# 1_cpu_control.net
KiCad netlist of a schematic drawn in EAGLE
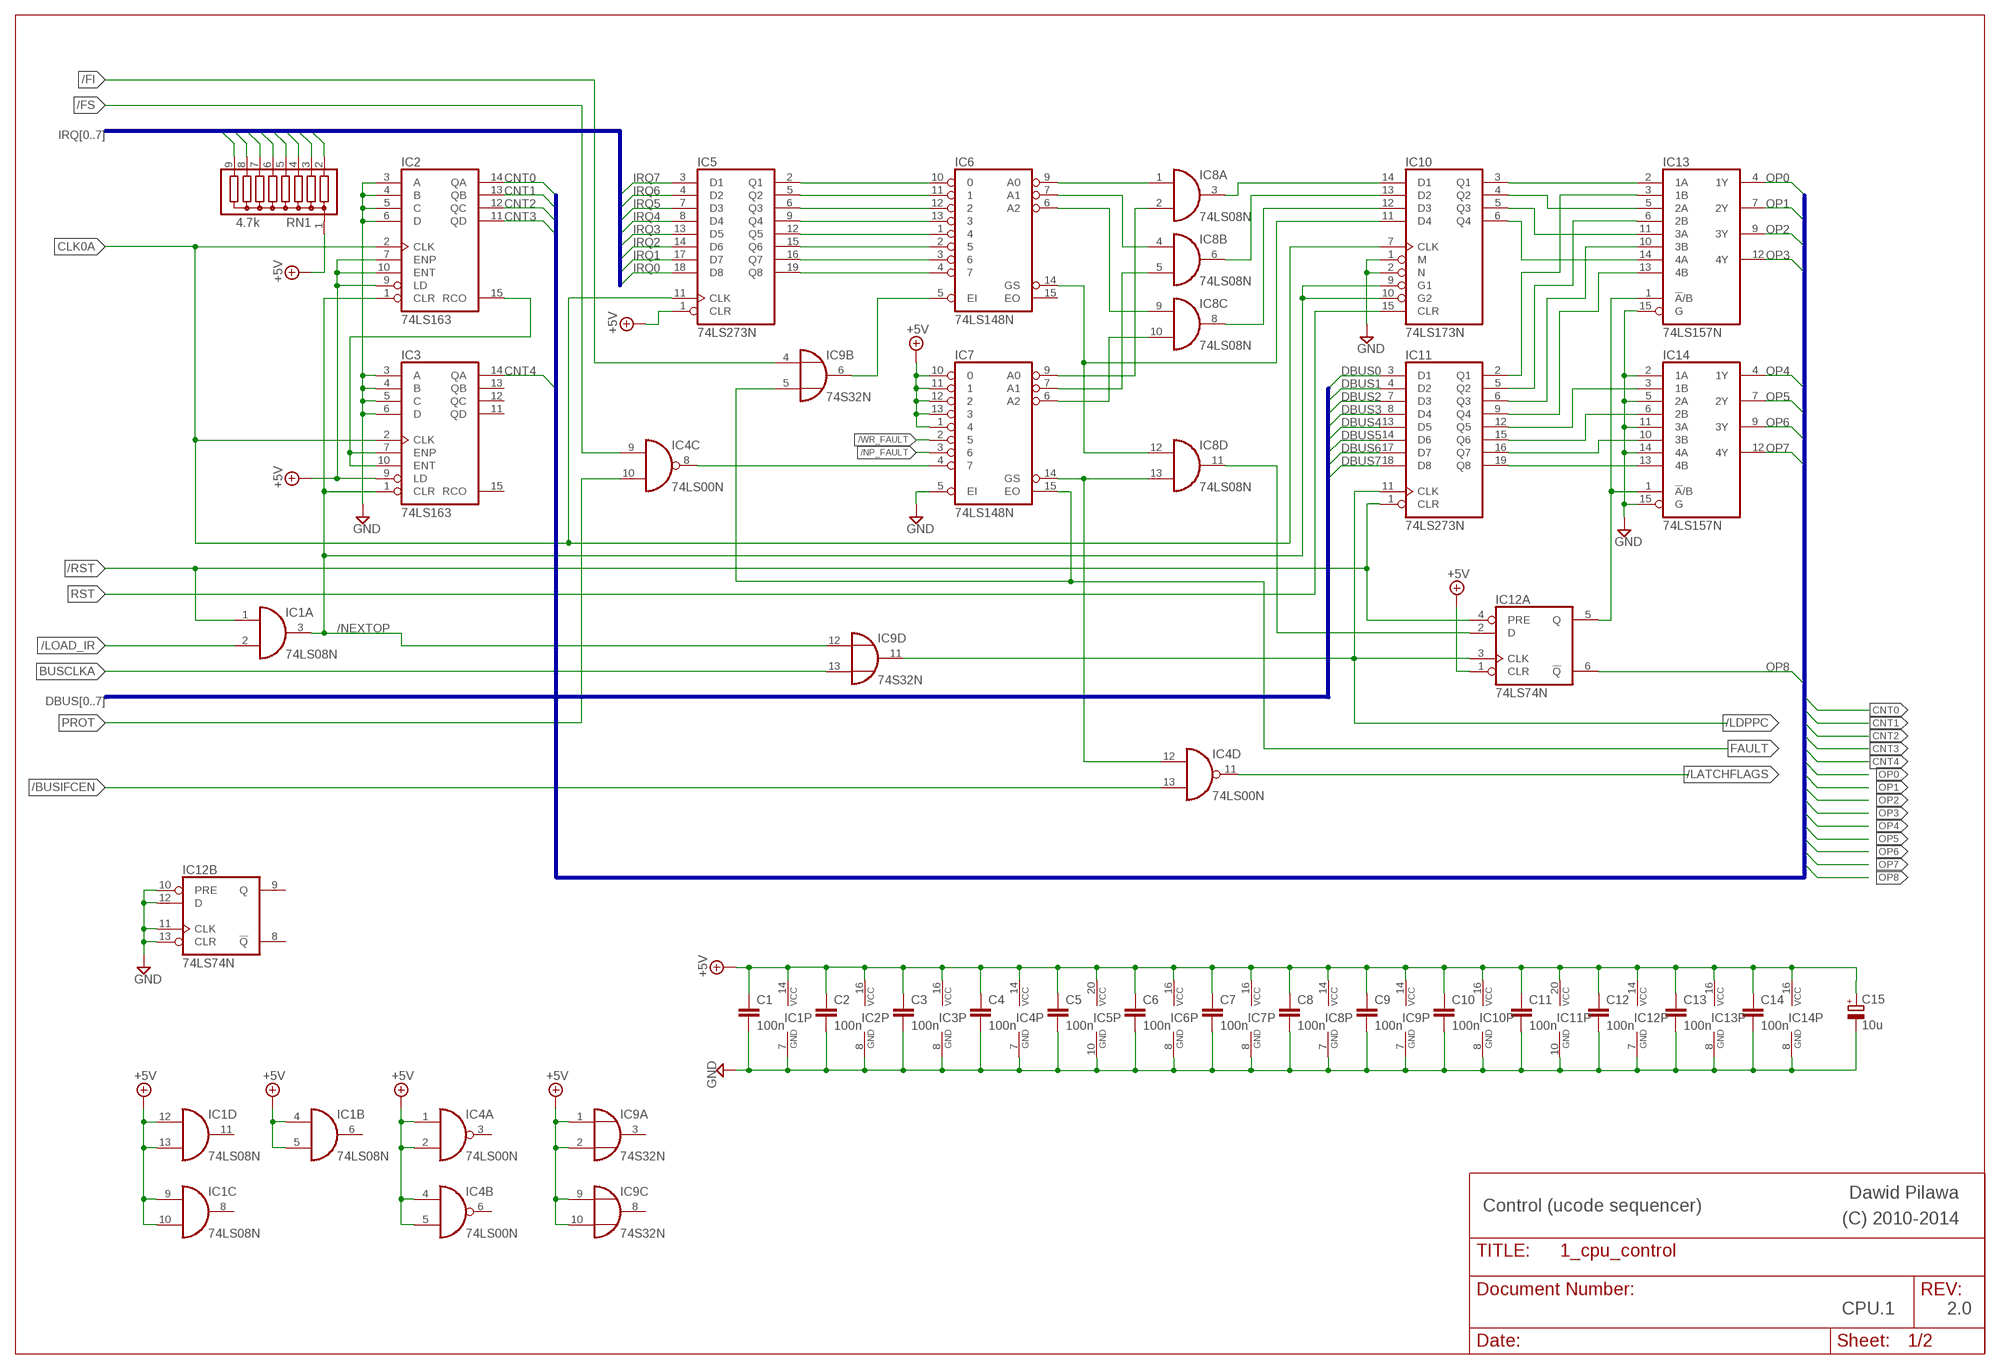
[diagram p0: schematic, sheet 1]
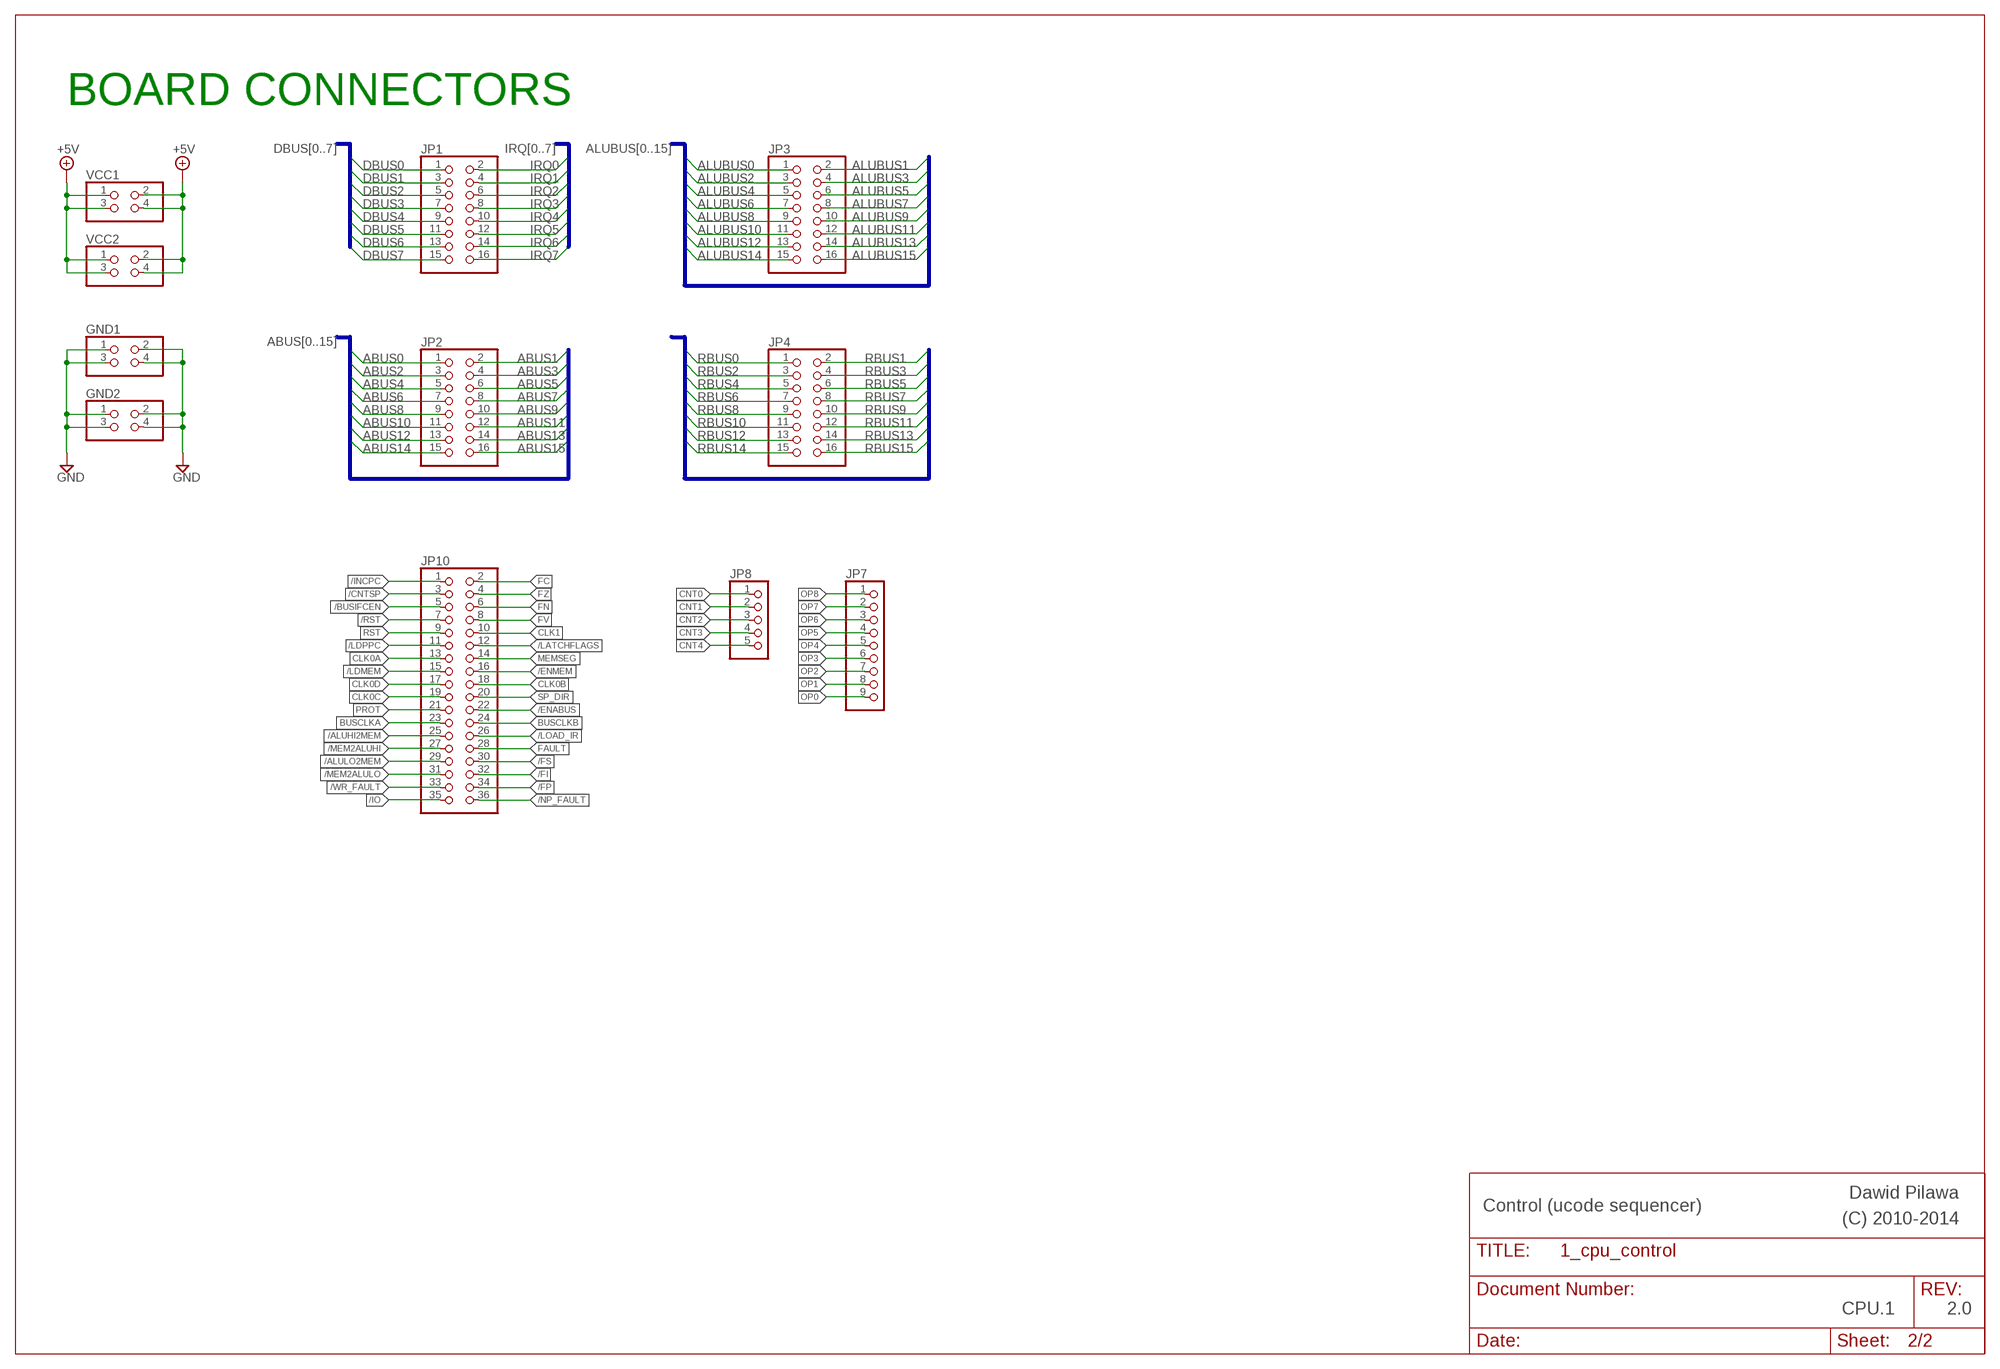
[diagram p1: schematic, sheet 2]

(export (version "E")
  (design (tool "Eeschema 10.0.6"))
  (components
    (comp (ref "GND1")
      (value "PINHD-2X2")
      (footprint "eagle-import:2X02")
      (libsource (lib "eagle-import") (part "PINHD-2X2"))
    )
    (comp (ref "GND2")
      (value "PINHD-2X2")
      (footprint "eagle-import:2X02")
      (libsource (lib "eagle-import") (part "PINHD-2X2"))
    )
    (comp (ref "JP1")
      (value "PINHD-2X8")
      (footprint "eagle-import:2X08")
      (libsource (lib "eagle-import") (part "PINHD-2X8"))
    )
    (comp (ref "JP2")
      (value "PINHD-2X8")
      (footprint "eagle-import:2X08")
      (libsource (lib "eagle-import") (part "PINHD-2X8"))
    )
    (comp (ref "JP3")
      (value "PINHD-2X8")
      (footprint "eagle-import:2X08")
      (libsource (lib "eagle-import") (part "PINHD-2X8"))
    )
    (comp (ref "JP4")
      (value "PINHD-2X8")
      (footprint "eagle-import:2X08")
      (libsource (lib "eagle-import") (part "PINHD-2X8"))
    )
    (comp (ref "JP7")
      (value "PINHD-1X9")
      (footprint "eagle-import:1X09")
      (libsource (lib "eagle-import") (part "PINHD-1X9"))
    )
    (comp (ref "JP8")
      (value "PINHD-1X5")
      (footprint "eagle-import:1X05")
      (libsource (lib "eagle-import") (part "PINHD-1X5"))
    )
    (comp (ref "JP10")
      (value "PINHD-2X18")
      (footprint "eagle-import:2X18")
      (libsource (lib "eagle-import") (part "PINHD-2X18"))
    )
    (comp (ref "VCC1")
      (value "PINHD-2X2")
      (footprint "eagle-import:2X02")
      (libsource (lib "eagle-import") (part "PINHD-2X2"))
    )
    (comp (ref "VCC2")
      (value "PINHD-2X2")
      (footprint "eagle-import:2X02")
      (libsource (lib "eagle-import") (part "PINHD-2X2"))
    )
    (comp (ref "C1")
      (value "100n")
      (footprint "eagle-import:C050-024X044")
      (libsource (lib "eagle-import") (part "C-EU050-024X044"))
    )
    (comp (ref "C2")
      (value "100n")
      (footprint "eagle-import:C050-024X044")
      (libsource (lib "eagle-import") (part "C-EU050-024X044"))
    )
    (comp (ref "C3")
      (value "100n")
      (footprint "eagle-import:C050-024X044")
      (libsource (lib "eagle-import") (part "C-EU050-024X044"))
    )
    (comp (ref "C4")
      (value "100n")
      (footprint "eagle-import:C050-024X044")
      (libsource (lib "eagle-import") (part "C-EU050-024X044"))
    )
    (comp (ref "C5")
      (value "100n")
      (footprint "eagle-import:C050-024X044")
      (libsource (lib "eagle-import") (part "C-EU050-024X044"))
    )
    (comp (ref "C6")
      (value "100n")
      (footprint "eagle-import:C050-024X044")
      (libsource (lib "eagle-import") (part "C-EU050-024X044"))
    )
    (comp (ref "C7")
      (value "100n")
      (footprint "eagle-import:C050-024X044")
      (libsource (lib "eagle-import") (part "C-EU050-024X044"))
    )
    (comp (ref "C8")
      (value "100n")
      (footprint "eagle-import:C050-024X044")
      (libsource (lib "eagle-import") (part "C-EU050-024X044"))
    )
    (comp (ref "C9")
      (value "100n")
      (footprint "eagle-import:C050-024X044")
      (libsource (lib "eagle-import") (part "C-EU050-024X044"))
    )
    (comp (ref "C10")
      (value "100n")
      (footprint "eagle-import:C050-024X044")
      (libsource (lib "eagle-import") (part "C-EU050-024X044"))
    )
    (comp (ref "C11")
      (value "100n")
      (footprint "eagle-import:C050-024X044")
      (libsource (lib "eagle-import") (part "C-EU050-024X044"))
    )
    (comp (ref "C12")
      (value "100n")
      (footprint "eagle-import:C050-024X044")
      (libsource (lib "eagle-import") (part "C-EU050-024X044"))
    )
    (comp (ref "C13")
      (value "100n")
      (footprint "eagle-import:C050-024X044")
      (libsource (lib "eagle-import") (part "C-EU050-024X044"))
    )
    (comp (ref "C14")
      (value "100n")
      (footprint "eagle-import:C050-024X044")
      (libsource (lib "eagle-import") (part "C-EU050-024X044"))
    )
    (comp (ref "C15")
      (value "10u")
      (footprint "eagle-import:E5-6")
      (libsource (lib "eagle-import") (part "CPOL-EUE5-6"))
    )
    (comp (ref "IC1")
      (value "74LS08N")
      (footprint "eagle-import:DIL14")
      (libsource (lib "eagle-import") (part "7408NLS"))
    )
    (comp (ref "IC2")
      (value "74LS163")
      (footprint "eagle-import:DIL16")
      (libsource (lib "eagle-import") (part "74160N"))
    )
    (comp (ref "IC3")
      (value "74LS163")
      (footprint "eagle-import:DIL16")
      (libsource (lib "eagle-import") (part "74160N"))
    )
    (comp (ref "IC4")
      (value "74LS00N")
      (footprint "eagle-import:DIL14")
      (libsource (lib "eagle-import") (part "7400NLS"))
    )
    (comp (ref "IC5")
      (value "74LS273N")
      (footprint "eagle-import:DIL20")
      (libsource (lib "eagle-import") (part "74273N"))
    )
    (comp (ref "IC6")
      (value "74LS148N")
      (footprint "eagle-import:DIL16")
      (libsource (lib "eagle-import") (part "74148NLS"))
    )
    (comp (ref "IC7")
      (value "74LS148N")
      (footprint "eagle-import:DIL16")
      (libsource (lib "eagle-import") (part "74148NLS"))
    )
    (comp (ref "IC8")
      (value "74LS08N")
      (footprint "eagle-import:DIL14")
      (libsource (lib "eagle-import") (part "7408NLS"))
    )
    (comp (ref "IC9")
      (value "74S32N")
      (footprint "eagle-import:DIL14")
      (libsource (lib "eagle-import") (part "7432NS"))
    )
    (comp (ref "IC10")
      (value "74LS173N")
      (footprint "eagle-import:DIL16")
      (libsource (lib "eagle-import") (part "74173NLS"))
    )
    (comp (ref "IC11")
      (value "74LS273N")
      (footprint "eagle-import:DIL20")
      (libsource (lib "eagle-import") (part "74273N"))
    )
    (comp (ref "IC12")
      (value "74LS74N")
      (footprint "eagle-import:DIL14")
      (libsource (lib "eagle-import") (part "7474NLS"))
    )
    (comp (ref "IC13")
      (value "74LS157N")
      (footprint "eagle-import:DIL16")
      (libsource (lib "eagle-import") (part "74157NLS"))
    )
    (comp (ref "IC14")
      (value "74LS157N")
      (footprint "eagle-import:DIL16")
      (libsource (lib "eagle-import") (part "74157NLS"))
    )
    (comp (ref "RN1")
      (value "4.7k")
      (footprint "eagle-import:SIL9")
      (libsource (lib "eagle-import") (part "G08R"))
    )
  )
  (nets
    (net (code "1") (name "+5V") (class "Default")
      (node (ref "C1") (pin "1") (pinfunction "1_1") (pintype "passive"))
      (node (ref "C10") (pin "1") (pinfunction "1_1") (pintype "passive"))
      (node (ref "C11") (pin "1") (pinfunction "1_1") (pintype "passive"))
      (node (ref "C12") (pin "1") (pinfunction "1_1") (pintype "passive"))
      (node (ref "C13") (pin "1") (pinfunction "1_1") (pintype "passive"))
      (node (ref "C14") (pin "1") (pinfunction "1_1") (pintype "passive"))
      (node (ref "C15") (pin "+") (pinfunction "+_+") (pintype "passive"))
      (node (ref "C2") (pin "1") (pinfunction "1_1") (pintype "passive"))
      (node (ref "C3") (pin "1") (pinfunction "1_1") (pintype "passive"))
      (node (ref "C4") (pin "1") (pinfunction "1_1") (pintype "passive"))
      (node (ref "C5") (pin "1") (pinfunction "1_1") (pintype "passive"))
      (node (ref "C6") (pin "1") (pinfunction "1_1") (pintype "passive"))
      (node (ref "C7") (pin "1") (pinfunction "1_1") (pintype "passive"))
      (node (ref "C8") (pin "1") (pinfunction "1_1") (pintype "passive"))
      (node (ref "C9") (pin "1") (pinfunction "1_1") (pintype "passive"))
      (node (ref "IC1") (pin "10") (pinfunction "I1_10") (pintype "input"))
      (node (ref "IC1") (pin "12") (pinfunction "I0_12") (pintype "input"))
      (node (ref "IC1") (pin "13") (pinfunction "I1_13") (pintype "input"))
      (node (ref "IC1") (pin "14") (pinfunction "VCC_14") (pintype "power_in"))
      (node (ref "IC1") (pin "4") (pinfunction "I0_4") (pintype "input"))
      (node (ref "IC1") (pin "5") (pinfunction "I1_5") (pintype "input"))
      (node (ref "IC1") (pin "9") (pinfunction "I0_9") (pintype "input"))
      (node (ref "IC10") (pin "16") (pinfunction "VCC_16") (pintype "power_in"))
      (node (ref "IC11") (pin "20") (pinfunction "VCC_20") (pintype "power_in"))
      (node (ref "IC12") (pin "1") (pinfunction "CLR_1") (pintype "input"))
      (node (ref "IC12") (pin "14") (pinfunction "VCC_14") (pintype "power_in"))
      (node (ref "IC13") (pin "16") (pinfunction "VCC_16") (pintype "power_in"))
      (node (ref "IC14") (pin "16") (pinfunction "VCC_16") (pintype "power_in"))
      (node (ref "IC2") (pin "10") (pinfunction "ENT_10") (pintype "input"))
      (node (ref "IC2") (pin "16") (pinfunction "VCC_16") (pintype "power_in"))
      (node (ref "IC2") (pin "7") (pinfunction "ENP_7") (pintype "input"))
      (node (ref "IC2") (pin "9") (pinfunction "LD_9") (pintype "input"))
      (node (ref "IC3") (pin "16") (pinfunction "VCC_16") (pintype "power_in"))
      (node (ref "IC3") (pin "9") (pinfunction "LD_9") (pintype "input"))
      (node (ref "IC4") (pin "1") (pinfunction "I0_1") (pintype "input"))
      (node (ref "IC4") (pin "14") (pinfunction "VCC_14") (pintype "power_in"))
      (node (ref "IC4") (pin "2") (pinfunction "I1_2") (pintype "input"))
      (node (ref "IC4") (pin "4") (pinfunction "I0_4") (pintype "input"))
      (node (ref "IC4") (pin "5") (pinfunction "I1_5") (pintype "input"))
      (node (ref "IC5") (pin "1") (pinfunction "CLR_1") (pintype "input"))
      (node (ref "IC5") (pin "20") (pinfunction "VCC_20") (pintype "power_in"))
      (node (ref "IC6") (pin "16") (pinfunction "VCC_16") (pintype "power_in"))
      (node (ref "IC7") (pin "1") (pinfunction "4_1") (pintype "input"))
      (node (ref "IC7") (pin "10") (pinfunction "0_10") (pintype "input"))
      (node (ref "IC7") (pin "11") (pinfunction "1_11") (pintype "input"))
      (node (ref "IC7") (pin "12") (pinfunction "2_12") (pintype "input"))
      (node (ref "IC7") (pin "13") (pinfunction "3_13") (pintype "input"))
      (node (ref "IC7") (pin "16") (pinfunction "VCC_16") (pintype "power_in"))
      (node (ref "IC8") (pin "14") (pinfunction "VCC_14") (pintype "power_in"))
      (node (ref "IC9") (pin "1") (pinfunction "I0_1") (pintype "input"))
      (node (ref "IC9") (pin "10") (pinfunction "I1_10") (pintype "input"))
      (node (ref "IC9") (pin "14") (pinfunction "VCC_14") (pintype "power_in"))
      (node (ref "IC9") (pin "2") (pinfunction "I1_2") (pintype "input"))
      (node (ref "IC9") (pin "9") (pinfunction "I0_9") (pintype "input"))
      (node (ref "RN1") (pin "1") (pinfunction "1_1") (pintype "passive"))
      (node (ref "VCC1") (pin "1") (pinfunction "1_1") (pintype "passive"))
      (node (ref "VCC1") (pin "2") (pinfunction "2_2") (pintype "passive"))
      (node (ref "VCC1") (pin "3") (pinfunction "3_3") (pintype "passive"))
      (node (ref "VCC1") (pin "4") (pinfunction "4_4") (pintype "passive"))
      (node (ref "VCC2") (pin "1") (pinfunction "1_1") (pintype "passive"))
      (node (ref "VCC2") (pin "2") (pinfunction "2_2") (pintype "passive"))
      (node (ref "VCC2") (pin "3") (pinfunction "3_3") (pintype "passive"))
      (node (ref "VCC2") (pin "4") (pinfunction "4_4") (pintype "passive"))
    )
    (net (code "8") (name "ABUS0") (class "Default")
      (node (ref "JP2") (pin "1") (pinfunction "1_1") (pintype "passive"))
    )
    (net (code "9") (name "ABUS1") (class "Default")
      (node (ref "JP2") (pin "2") (pinfunction "2_2") (pintype "passive"))
    )
    (net (code "10") (name "ABUS2") (class "Default")
      (node (ref "JP2") (pin "3") (pinfunction "3_3") (pintype "passive"))
    )
    (net (code "11") (name "ABUS3") (class "Default")
      (node (ref "JP2") (pin "4") (pinfunction "4_4") (pintype "passive"))
    )
    (net (code "12") (name "ABUS4") (class "Default")
      (node (ref "JP2") (pin "5") (pinfunction "5_5") (pintype "passive"))
    )
    (net (code "13") (name "ABUS5") (class "Default")
      (node (ref "JP2") (pin "6") (pinfunction "6_6") (pintype "passive"))
    )
    (net (code "14") (name "ABUS6") (class "Default")
      (node (ref "JP2") (pin "7") (pinfunction "7_7") (pintype "passive"))
    )
    (net (code "15") (name "ABUS7") (class "Default")
      (node (ref "JP2") (pin "8") (pinfunction "8_8") (pintype "passive"))
    )
    (net (code "16") (name "ABUS8") (class "Default")
      (node (ref "JP2") (pin "9") (pinfunction "9_9") (pintype "passive"))
    )
    (net (code "17") (name "ABUS9") (class "Default")
      (node (ref "JP2") (pin "10") (pinfunction "10_10") (pintype "passive"))
    )
    (net (code "18") (name "ABUS10") (class "Default")
      (node (ref "JP2") (pin "11") (pinfunction "11_11") (pintype "passive"))
    )
    (net (code "19") (name "ABUS11") (class "Default")
      (node (ref "JP2") (pin "12") (pinfunction "12_12") (pintype "passive"))
    )
    (net (code "20") (name "ABUS12") (class "Default")
      (node (ref "JP2") (pin "13") (pinfunction "13_13") (pintype "passive"))
    )
    (net (code "21") (name "ABUS13") (class "Default")
      (node (ref "JP2") (pin "14") (pinfunction "14_14") (pintype "passive"))
    )
    (net (code "22") (name "ABUS14") (class "Default")
      (node (ref "JP2") (pin "15") (pinfunction "15_15") (pintype "passive"))
    )
    (net (code "23") (name "ABUS15") (class "Default")
      (node (ref "JP2") (pin "16") (pinfunction "16_16") (pintype "passive"))
    )
    (net (code "24") (name "ALUBUS0") (class "Default")
      (node (ref "JP3") (pin "1") (pinfunction "1_1") (pintype "passive"))
    )
    (net (code "25") (name "ALUBUS1") (class "Default")
      (node (ref "JP3") (pin "2") (pinfunction "2_2") (pintype "passive"))
    )
    (net (code "26") (name "ALUBUS2") (class "Default")
      (node (ref "JP3") (pin "3") (pinfunction "3_3") (pintype "passive"))
    )
    (net (code "27") (name "ALUBUS3") (class "Default")
      (node (ref "JP3") (pin "4") (pinfunction "4_4") (pintype "passive"))
    )
    (net (code "28") (name "ALUBUS4") (class "Default")
      (node (ref "JP3") (pin "5") (pinfunction "5_5") (pintype "passive"))
    )
    (net (code "29") (name "ALUBUS5") (class "Default")
      (node (ref "JP3") (pin "6") (pinfunction "6_6") (pintype "passive"))
    )
    (net (code "30") (name "ALUBUS6") (class "Default")
      (node (ref "JP3") (pin "7") (pinfunction "7_7") (pintype "passive"))
    )
    (net (code "31") (name "ALUBUS7") (class "Default")
      (node (ref "JP3") (pin "8") (pinfunction "8_8") (pintype "passive"))
    )
    (net (code "32") (name "ALUBUS8") (class "Default")
      (node (ref "JP3") (pin "9") (pinfunction "9_9") (pintype "passive"))
    )
    (net (code "33") (name "ALUBUS9") (class "Default")
      (node (ref "JP3") (pin "10") (pinfunction "10_10") (pintype "passive"))
    )
    (net (code "34") (name "ALUBUS10") (class "Default")
      (node (ref "JP3") (pin "11") (pinfunction "11_11") (pintype "passive"))
    )
    (net (code "35") (name "ALUBUS11") (class "Default")
      (node (ref "JP3") (pin "12") (pinfunction "12_12") (pintype "passive"))
    )
    (net (code "36") (name "ALUBUS12") (class "Default")
      (node (ref "JP3") (pin "13") (pinfunction "13_13") (pintype "passive"))
    )
    (net (code "37") (name "ALUBUS13") (class "Default")
      (node (ref "JP3") (pin "14") (pinfunction "14_14") (pintype "passive"))
    )
    (net (code "38") (name "ALUBUS14") (class "Default")
      (node (ref "JP3") (pin "15") (pinfunction "15_15") (pintype "passive"))
    )
    (net (code "39") (name "ALUBUS15") (class "Default")
      (node (ref "JP3") (pin "16") (pinfunction "16_16") (pintype "passive"))
    )
    (net (code "40") (name "BUSCLKA") (class "Default")
      (node (ref "IC9") (pin "13") (pinfunction "I1_13") (pintype "input"))
      (node (ref "JP10") (pin "23") (pinfunction "23_23") (pintype "passive"))
    )
    (net (code "41") (name "BUSCLKB") (class "Default")
      (node (ref "JP10") (pin "24") (pinfunction "24_24") (pintype "passive"))
    )
    (net (code "42") (name "CLK0A") (class "Default")
      (node (ref "IC10") (pin "7") (pinfunction "CLK_7") (pintype "input"))
      (node (ref "IC2") (pin "2") (pinfunction "CLK_2") (pintype "input"))
      (node (ref "IC3") (pin "2") (pinfunction "CLK_2") (pintype "input"))
      (node (ref "IC5") (pin "11") (pinfunction "CLK_11") (pintype "input"))
      (node (ref "JP10") (pin "13") (pinfunction "13_13") (pintype "passive"))
    )
    (net (code "43") (name "CLK0B") (class "Default")
      (node (ref "JP10") (pin "18") (pinfunction "18_18") (pintype "passive"))
    )
    (net (code "44") (name "CLK0C") (class "Default")
      (node (ref "JP10") (pin "19") (pinfunction "19_19") (pintype "passive"))
    )
    (net (code "45") (name "CLK0D") (class "Default")
      (node (ref "JP10") (pin "17") (pinfunction "17_17") (pintype "passive"))
    )
    (net (code "46") (name "CLK1") (class "Default")
      (node (ref "JP10") (pin "10") (pinfunction "10_10") (pintype "passive"))
    )
    (net (code "47") (name "CNT0") (class "Default")
      (node (ref "IC2") (pin "14") (pinfunction "QA_14") (pintype "output"))
      (node (ref "JP8") (pin "1") (pinfunction "1_1") (pintype "passive"))
    )
    (net (code "48") (name "CNT1") (class "Default")
      (node (ref "IC2") (pin "13") (pinfunction "QB_13") (pintype "output"))
      (node (ref "JP8") (pin "2") (pinfunction "2_2") (pintype "passive"))
    )
    (net (code "49") (name "CNT2") (class "Default")
      (node (ref "IC2") (pin "12") (pinfunction "QC_12") (pintype "output"))
      (node (ref "JP8") (pin "3") (pinfunction "3_3") (pintype "passive"))
    )
    (net (code "50") (name "CNT3") (class "Default")
      (node (ref "IC2") (pin "11") (pinfunction "QD_11") (pintype "output"))
      (node (ref "JP8") (pin "4") (pinfunction "4_4") (pintype "passive"))
    )
    (net (code "51") (name "CNT4") (class "Default")
      (node (ref "IC3") (pin "14") (pinfunction "QA_14") (pintype "output"))
      (node (ref "JP8") (pin "5") (pinfunction "5_5") (pintype "passive"))
    )
    (net (code "52") (name "DBUS0") (class "Default")
      (node (ref "IC11") (pin "3") (pinfunction "D1_3") (pintype "input"))
      (node (ref "JP1") (pin "1") (pinfunction "1_1") (pintype "passive"))
    )
    (net (code "53") (name "DBUS1") (class "Default")
      (node (ref "IC11") (pin "4") (pinfunction "D2_4") (pintype "input"))
      (node (ref "JP1") (pin "3") (pinfunction "3_3") (pintype "passive"))
    )
    (net (code "54") (name "DBUS2") (class "Default")
      (node (ref "IC11") (pin "7") (pinfunction "D3_7") (pintype "input"))
      (node (ref "JP1") (pin "5") (pinfunction "5_5") (pintype "passive"))
    )
    (net (code "55") (name "DBUS3") (class "Default")
      (node (ref "IC11") (pin "8") (pinfunction "D4_8") (pintype "input"))
      (node (ref "JP1") (pin "7") (pinfunction "7_7") (pintype "passive"))
    )
    (net (code "56") (name "DBUS4") (class "Default")
      (node (ref "IC11") (pin "13") (pinfunction "D5_13") (pintype "input"))
      (node (ref "JP1") (pin "9") (pinfunction "9_9") (pintype "passive"))
    )
    (net (code "57") (name "DBUS5") (class "Default")
      (node (ref "IC11") (pin "14") (pinfunction "D6_14") (pintype "input"))
      (node (ref "JP1") (pin "11") (pinfunction "11_11") (pintype "passive"))
    )
    (net (code "58") (name "DBUS6") (class "Default")
      (node (ref "IC11") (pin "17") (pinfunction "D7_17") (pintype "input"))
      (node (ref "JP1") (pin "13") (pinfunction "13_13") (pintype "passive"))
    )
    (net (code "59") (name "DBUS7") (class "Default")
      (node (ref "IC11") (pin "18") (pinfunction "D8_18") (pintype "input"))
      (node (ref "JP1") (pin "15") (pinfunction "15_15") (pintype "passive"))
    )
    (net (code "60") (name "FAULT") (class "Default")
      (node (ref "IC7") (pin "15") (pinfunction "EO_15") (pintype "output"))
      (node (ref "IC9") (pin "5") (pinfunction "I1_5") (pintype "input"))
      (node (ref "JP10") (pin "28") (pinfunction "28_28") (pintype "passive"))
    )
    (net (code "61") (name "FC") (class "Default")
      (node (ref "JP10") (pin "2") (pinfunction "2_2") (pintype "passive"))
    )
    (net (code "62") (name "FN") (class "Default")
      (node (ref "JP10") (pin "6") (pinfunction "6_6") (pintype "passive"))
    )
    (net (code "63") (name "FV") (class "Default")
      (node (ref "JP10") (pin "8") (pinfunction "8_8") (pintype "passive"))
    )
    (net (code "64") (name "FZ") (class "Default")
      (node (ref "JP10") (pin "4") (pinfunction "4_4") (pintype "passive"))
    )
    (net (code "65") (name "GND") (class "Default")
      (node (ref "C1") (pin "2") (pinfunction "2_2") (pintype "passive"))
      (node (ref "C10") (pin "2") (pinfunction "2_2") (pintype "passive"))
      (node (ref "C11") (pin "2") (pinfunction "2_2") (pintype "passive"))
      (node (ref "C12") (pin "2") (pinfunction "2_2") (pintype "passive"))
      (node (ref "C13") (pin "2") (pinfunction "2_2") (pintype "passive"))
      (node (ref "C14") (pin "2") (pinfunction "2_2") (pintype "passive"))
      (node (ref "C15") (pin "-") (pinfunction "-_-") (pintype "passive"))
      (node (ref "C2") (pin "2") (pinfunction "2_2") (pintype "passive"))
      (node (ref "C3") (pin "2") (pinfunction "2_2") (pintype "passive"))
      (node (ref "C4") (pin "2") (pinfunction "2_2") (pintype "passive"))
      (node (ref "C5") (pin "2") (pinfunction "2_2") (pintype "passive"))
      (node (ref "C6") (pin "2") (pinfunction "2_2") (pintype "passive"))
      (node (ref "C7") (pin "2") (pinfunction "2_2") (pintype "passive"))
      (node (ref "C8") (pin "2") (pinfunction "2_2") (pintype "passive"))
      (node (ref "C9") (pin "2") (pinfunction "2_2") (pintype "passive"))
      (node (ref "GND1") (pin "1") (pinfunction "1_1") (pintype "passive"))
      (node (ref "GND1") (pin "2") (pinfunction "2_2") (pintype "passive"))
      (node (ref "GND1") (pin "3") (pinfunction "3_3") (pintype "passive"))
      (node (ref "GND1") (pin "4") (pinfunction "4_4") (pintype "passive"))
      (node (ref "GND2") (pin "1") (pinfunction "1_1") (pintype "passive"))
      (node (ref "GND2") (pin "2") (pinfunction "2_2") (pintype "passive"))
      (node (ref "GND2") (pin "3") (pinfunction "3_3") (pintype "passive"))
      (node (ref "GND2") (pin "4") (pinfunction "4_4") (pintype "passive"))
      (node (ref "IC1") (pin "7") (pinfunction "GND_7") (pintype "power_in"))
      (node (ref "IC10") (pin "1") (pinfunction "M_1") (pintype "input"))
      (node (ref "IC10") (pin "2") (pinfunction "N_2") (pintype "input"))
      (node (ref "IC10") (pin "8") (pinfunction "GND_8") (pintype "power_in"))
      (node (ref "IC11") (pin "10") (pinfunction "GND_10") (pintype "power_in"))
      (node (ref "IC12") (pin "10") (pinfunction "PRE_10") (pintype "input"))
      (node (ref "IC12") (pin "11") (pinfunction "CLK_11") (pintype "input"))
      (node (ref "IC12") (pin "12") (pinfunction "D_12") (pintype "input"))
      (node (ref "IC12") (pin "13") (pinfunction "CLR_13") (pintype "input"))
      (node (ref "IC12") (pin "7") (pinfunction "GND_7") (pintype "power_in"))
      (node (ref "IC13") (pin "15") (pinfunction "G_15") (pintype "input"))
      (node (ref "IC13") (pin "8") (pinfunction "GND_8") (pintype "power_in"))
      (node (ref "IC14") (pin "11") (pinfunction "3A_11") (pintype "input"))
      (node (ref "IC14") (pin "14") (pinfunction "4A_14") (pintype "input"))
      (node (ref "IC14") (pin "15") (pinfunction "G_15") (pintype "input"))
      (node (ref "IC14") (pin "2") (pinfunction "1A_2") (pintype "input"))
      (node (ref "IC14") (pin "5") (pinfunction "2A_5") (pintype "input"))
      (node (ref "IC14") (pin "8") (pinfunction "GND_8") (pintype "power_in"))
      (node (ref "IC2") (pin "3") (pinfunction "A_3") (pintype "input"))
      (node (ref "IC2") (pin "4") (pinfunction "B_4") (pintype "input"))
      (node (ref "IC2") (pin "5") (pinfunction "C_5") (pintype "input"))
      (node (ref "IC2") (pin "6") (pinfunction "D_6") (pintype "input"))
      (node (ref "IC2") (pin "8") (pinfunction "GND_8") (pintype "power_in"))
      (node (ref "IC3") (pin "3") (pinfunction "A_3") (pintype "input"))
      (node (ref "IC3") (pin "4") (pinfunction "B_4") (pintype "input"))
      (node (ref "IC3") (pin "5") (pinfunction "C_5") (pintype "input"))
      (node (ref "IC3") (pin "6") (pinfunction "D_6") (pintype "input"))
      (node (ref "IC3") (pin "8") (pinfunction "GND_8") (pintype "power_in"))
      (node (ref "IC4") (pin "7") (pinfunction "GND_7") (pintype "power_in"))
      (node (ref "IC5") (pin "10") (pinfunction "GND_10") (pintype "power_in"))
      (node (ref "IC6") (pin "8") (pinfunction "GND_8") (pintype "power_in"))
      (node (ref "IC7") (pin "5") (pinfunction "EI_5") (pintype "input"))
      (node (ref "IC7") (pin "8") (pinfunction "GND_8") (pintype "power_in"))
      (node (ref "IC8") (pin "7") (pinfunction "GND_7") (pintype "power_in"))
      (node (ref "IC9") (pin "7") (pinfunction "GND_7") (pintype "power_in"))
    )
    (net (code "66") (name "IRQ0") (class "Default")
      (node (ref "IC5") (pin "18") (pinfunction "D8_18") (pintype "input"))
      (node (ref "JP1") (pin "2") (pinfunction "2_2") (pintype "passive"))
      (node (ref "RN1") (pin "9") (pinfunction "9_9") (pintype "passive"))
    )
    (net (code "67") (name "IRQ1") (class "Default")
      (node (ref "IC5") (pin "17") (pinfunction "D7_17") (pintype "input"))
      (node (ref "JP1") (pin "4") (pinfunction "4_4") (pintype "passive"))
      (node (ref "RN1") (pin "8") (pinfunction "8_8") (pintype "passive"))
    )
    (net (code "68") (name "IRQ2") (class "Default")
      (node (ref "IC5") (pin "14") (pinfunction "D6_14") (pintype "input"))
      (node (ref "JP1") (pin "6") (pinfunction "6_6") (pintype "passive"))
      (node (ref "RN1") (pin "7") (pinfunction "7_7") (pintype "passive"))
    )
    (net (code "69") (name "IRQ3") (class "Default")
      (node (ref "IC5") (pin "13") (pinfunction "D5_13") (pintype "input"))
      (node (ref "JP1") (pin "8") (pinfunction "8_8") (pintype "passive"))
      (node (ref "RN1") (pin "6") (pinfunction "6_6") (pintype "passive"))
    )
    (net (code "70") (name "IRQ4") (class "Default")
      (node (ref "IC5") (pin "8") (pinfunction "D4_8") (pintype "input"))
      (node (ref "JP1") (pin "10") (pinfunction "10_10") (pintype "passive"))
      (node (ref "RN1") (pin "5") (pinfunction "5_5") (pintype "passive"))
    )
    (net (code "71") (name "IRQ5") (class "Default")
      (node (ref "IC5") (pin "7") (pinfunction "D3_7") (pintype "input"))
      (node (ref "JP1") (pin "12") (pinfunction "12_12") (pintype "passive"))
      (node (ref "RN1") (pin "4") (pinfunction "4_4") (pintype "passive"))
    )
    (net (code "72") (name "IRQ6") (class "Default")
      (node (ref "IC5") (pin "4") (pinfunction "D2_4") (pintype "input"))
      (node (ref "JP1") (pin "14") (pinfunction "14_14") (pintype "passive"))
      (node (ref "RN1") (pin "3") (pinfunction "3_3") (pintype "passive"))
    )
    (net (code "73") (name "IRQ7") (class "Default")
      (node (ref "IC5") (pin "3") (pinfunction "D1_3") (pintype "input"))
      (node (ref "JP1") (pin "16") (pinfunction "16_16") (pintype "passive"))
      (node (ref "RN1") (pin "2") (pinfunction "2_2") (pintype "passive"))
    )
    (net (code "74") (name "MEMSEG") (class "Default")
      (node (ref "JP10") (pin "14") (pinfunction "14_14") (pintype "passive"))
    )
    (net (code "75") (name "Net-(IC2A-RCO)") (class "Default")
      (node (ref "IC2") (pin "15") (pinfunction "RCO_15") (pintype "output"))
      (node (ref "IC3") (pin "10") (pinfunction "ENT_10") (pintype "input"))
      (node (ref "IC3") (pin "7") (pinfunction "ENP_7") (pintype "input"))
    )
    (net (code "76") (name "Net-(IC4C-O)") (class "Default")
      (node (ref "IC4") (pin "8") (pinfunction "O_8") (pintype "output"))
      (node (ref "IC7") (pin "4") (pinfunction "7_4") (pintype "input"))
    )
    (net (code "77") (name "Net-(IC4D-I0)") (class "Default")
      (node (ref "IC4") (pin "12") (pinfunction "I0_12") (pintype "input"))
      (node (ref "IC7") (pin "14") (pinfunction "GS_14") (pintype "output"))
      (node (ref "IC8") (pin "13") (pinfunction "I1_13") (pintype "input"))
    )
    (net (code "78") (name "Net-(IC5A-Q1)") (class "Default")
      (node (ref "IC5") (pin "2") (pinfunction "Q1_2") (pintype "output"))
      (node (ref "IC6") (pin "10") (pinfunction "0_10") (pintype "input"))
    )
    (net (code "79") (name "Net-(IC5A-Q2)") (class "Default")
      (node (ref "IC5") (pin "5") (pinfunction "Q2_5") (pintype "output"))
      (node (ref "IC6") (pin "11") (pinfunction "1_11") (pintype "input"))
    )
    (net (code "80") (name "Net-(IC5A-Q3)") (class "Default")
      (node (ref "IC5") (pin "6") (pinfunction "Q3_6") (pintype "output"))
      (node (ref "IC6") (pin "12") (pinfunction "2_12") (pintype "input"))
    )
    (net (code "81") (name "Net-(IC5A-Q4)") (class "Default")
      (node (ref "IC5") (pin "9") (pinfunction "Q4_9") (pintype "output"))
      (node (ref "IC6") (pin "13") (pinfunction "3_13") (pintype "input"))
    )
    (net (code "82") (name "Net-(IC5A-Q5)") (class "Default")
      (node (ref "IC5") (pin "12") (pinfunction "Q5_12") (pintype "output"))
      (node (ref "IC6") (pin "1") (pinfunction "4_1") (pintype "input"))
    )
    (net (code "83") (name "Net-(IC5A-Q6)") (class "Default")
      (node (ref "IC5") (pin "15") (pinfunction "Q6_15") (pintype "output"))
      (node (ref "IC6") (pin "2") (pinfunction "5_2") (pintype "input"))
    )
    (net (code "84") (name "Net-(IC5A-Q7)") (class "Default")
      (node (ref "IC5") (pin "16") (pinfunction "Q7_16") (pintype "output"))
      (node (ref "IC6") (pin "3") (pinfunction "6_3") (pintype "input"))
    )
    (net (code "85") (name "Net-(IC5A-Q8)") (class "Default")
      (node (ref "IC5") (pin "19") (pinfunction "Q8_19") (pintype "output"))
      (node (ref "IC6") (pin "4") (pinfunction "7_4") (pintype "input"))
    )
    (net (code "86") (name "Net-(IC6A-A0)") (class "Default")
      (node (ref "IC6") (pin "9") (pinfunction "A0_9") (pintype "output"))
      (node (ref "IC8") (pin "1") (pinfunction "I0_1") (pintype "input"))
    )
    (net (code "87") (name "Net-(IC6A-A1)") (class "Default")
      (node (ref "IC6") (pin "7") (pinfunction "A1_7") (pintype "output"))
      (node (ref "IC8") (pin "4") (pinfunction "I0_4") (pintype "input"))
    )
    (net (code "88") (name "Net-(IC6A-A2)") (class "Default")
      (node (ref "IC6") (pin "6") (pinfunction "A2_6") (pintype "output"))
      (node (ref "IC8") (pin "9") (pinfunction "I0_9") (pintype "input"))
    )
    (net (code "89") (name "Net-(IC6A-EI)") (class "Default")
      (node (ref "IC6") (pin "5") (pinfunction "EI_5") (pintype "input"))
      (node (ref "IC9") (pin "6") (pinfunction "O_6") (pintype "output"))
    )
    (net (code "90") (name "Net-(IC7A-A0)") (class "Default")
      (node (ref "IC7") (pin "9") (pinfunction "A0_9") (pintype "output"))
      (node (ref "IC8") (pin "2") (pinfunction "I1_2") (pintype "input"))
    )
    (net (code "91") (name "Net-(IC7A-A1)") (class "Default")
      (node (ref "IC7") (pin "7") (pinfunction "A1_7") (pintype "output"))
      (node (ref "IC8") (pin "5") (pinfunction "I1_5") (pintype "input"))
    )
    (net (code "92") (name "Net-(IC7A-A2)") (class "Default")
      (node (ref "IC7") (pin "6") (pinfunction "A2_6") (pintype "output"))
      (node (ref "IC8") (pin "10") (pinfunction "I1_10") (pintype "input"))
    )
    (net (code "93") (name "Net-(IC10A-D1)") (class "Default")
      (node (ref "IC10") (pin "14") (pinfunction "D1_14") (pintype "input"))
      (node (ref "IC8") (pin "3") (pinfunction "O_3") (pintype "output"))
    )
    (net (code "94") (name "Net-(IC10A-D2)") (class "Default")
      (node (ref "IC10") (pin "13") (pinfunction "D2_13") (pintype "input"))
      (node (ref "IC8") (pin "6") (pinfunction "O_6") (pintype "output"))
    )
    (net (code "95") (name "Net-(IC10A-D3)") (class "Default")
      (node (ref "IC10") (pin "12") (pinfunction "D3_12") (pintype "input"))
      (node (ref "IC8") (pin "8") (pinfunction "O_8") (pintype "output"))
    )
    (net (code "96") (name "Net-(IC10A-D4)") (class "Default")
      (node (ref "IC10") (pin "11") (pinfunction "D4_11") (pintype "input"))
      (node (ref "IC6") (pin "14") (pinfunction "GS_14") (pintype "output"))
      (node (ref "IC8") (pin "12") (pinfunction "I0_12") (pintype "input"))
    )
    (net (code "97") (name "Net-(IC10A-Q1)") (class "Default")
      (node (ref "IC10") (pin "3") (pinfunction "Q1_3") (pintype "tri_state"))
      (node (ref "IC13") (pin "2") (pinfunction "1A_2") (pintype "input"))
    )
    (net (code "98") (name "Net-(IC10A-Q2)") (class "Default")
      (node (ref "IC10") (pin "4") (pinfunction "Q2_4") (pintype "tri_state"))
      (node (ref "IC13") (pin "5") (pinfunction "2A_5") (pintype "input"))
    )
    (net (code "99") (name "Net-(IC10A-Q3)") (class "Default")
      (node (ref "IC10") (pin "5") (pinfunction "Q3_5") (pintype "tri_state"))
      (node (ref "IC13") (pin "11") (pinfunction "3A_11") (pintype "input"))
    )
    (net (code "100") (name "Net-(IC10A-Q4)") (class "Default")
      (node (ref "IC10") (pin "6") (pinfunction "Q4_6") (pintype "tri_state"))
      (node (ref "IC13") (pin "14") (pinfunction "4A_14") (pintype "input"))
    )
    (net (code "101") (name "Net-(IC11A-Q1)") (class "Default")
      (node (ref "IC11") (pin "2") (pinfunction "Q1_2") (pintype "output"))
      (node (ref "IC13") (pin "3") (pinfunction "1B_3") (pintype "input"))
    )
    (net (code "102") (name "Net-(IC11A-Q2)") (class "Default")
      (node (ref "IC11") (pin "5") (pinfunction "Q2_5") (pintype "output"))
      (node (ref "IC13") (pin "6") (pinfunction "2B_6") (pintype "input"))
    )
    (net (code "103") (name "Net-(IC11A-Q3)") (class "Default")
      (node (ref "IC11") (pin "6") (pinfunction "Q3_6") (pintype "output"))
      (node (ref "IC13") (pin "10") (pinfunction "3B_10") (pintype "input"))
    )
    (net (code "104") (name "Net-(IC11A-Q4)") (class "Default")
      (node (ref "IC11") (pin "9") (pinfunction "Q4_9") (pintype "output"))
      (node (ref "IC13") (pin "13") (pinfunction "4B_13") (pintype "input"))
    )
    (net (code "105") (name "Net-(IC11A-Q5)") (class "Default")
      (node (ref "IC11") (pin "12") (pinfunction "Q5_12") (pintype "output"))
      (node (ref "IC14") (pin "3") (pinfunction "1B_3") (pintype "input"))
    )
    (net (code "106") (name "Net-(IC11A-Q6)") (class "Default")
      (node (ref "IC11") (pin "15") (pinfunction "Q6_15") (pintype "output"))
      (node (ref "IC14") (pin "6") (pinfunction "2B_6") (pintype "input"))
    )
    (net (code "107") (name "Net-(IC11A-Q7)") (class "Default")
      (node (ref "IC11") (pin "16") (pinfunction "Q7_16") (pintype "output"))
      (node (ref "IC14") (pin "10") (pinfunction "3B_10") (pintype "input"))
    )
    (net (code "108") (name "Net-(IC11A-Q8)") (class "Default")
      (node (ref "IC11") (pin "19") (pinfunction "Q8_19") (pintype "output"))
      (node (ref "IC14") (pin "13") (pinfunction "4B_13") (pintype "input"))
    )
    (net (code "109") (name "Net-(IC12A-D)") (class "Default")
      (node (ref "IC12") (pin "2") (pinfunction "D_2") (pintype "input"))
      (node (ref "IC8") (pin "11") (pinfunction "O_11") (pintype "output"))
    )
    (net (code "110") (name "Net-(IC12A-Q)") (class "Default")
      (node (ref "IC12") (pin "5") (pinfunction "Q_5") (pintype "output"))
      (node (ref "IC13") (pin "1") (pinfunction "~{A}/B_1") (pintype "input"))
      (node (ref "IC14") (pin "1") (pinfunction "~{A}/B_1") (pintype "input"))
    )
    (net (code "111") (name "OP0") (class "Default")
      (node (ref "IC13") (pin "4") (pinfunction "1Y_4") (pintype "output"))
      (node (ref "JP7") (pin "9") (pinfunction "9_9") (pintype "passive"))
    )
    (net (code "112") (name "OP1") (class "Default")
      (node (ref "IC13") (pin "7") (pinfunction "2Y_7") (pintype "output"))
      (node (ref "JP7") (pin "8") (pinfunction "8_8") (pintype "passive"))
    )
    (net (code "113") (name "OP2") (class "Default")
      (node (ref "IC13") (pin "9") (pinfunction "3Y_9") (pintype "output"))
      (node (ref "JP7") (pin "7") (pinfunction "7_7") (pintype "passive"))
    )
    (net (code "114") (name "OP3") (class "Default")
      (node (ref "IC13") (pin "12") (pinfunction "4Y_12") (pintype "output"))
      (node (ref "JP7") (pin "6") (pinfunction "6_6") (pintype "passive"))
    )
    (net (code "115") (name "OP4") (class "Default")
      (node (ref "IC14") (pin "4") (pinfunction "1Y_4") (pintype "output"))
      (node (ref "JP7") (pin "5") (pinfunction "5_5") (pintype "passive"))
    )
    (net (code "116") (name "OP5") (class "Default")
      (node (ref "IC14") (pin "7") (pinfunction "2Y_7") (pintype "output"))
      (node (ref "JP7") (pin "4") (pinfunction "4_4") (pintype "passive"))
    )
    (net (code "117") (name "OP6") (class "Default")
      (node (ref "IC14") (pin "9") (pinfunction "3Y_9") (pintype "output"))
      (node (ref "JP7") (pin "3") (pinfunction "3_3") (pintype "passive"))
    )
    (net (code "118") (name "OP7") (class "Default")
      (node (ref "IC14") (pin "12") (pinfunction "4Y_12") (pintype "output"))
      (node (ref "JP7") (pin "2") (pinfunction "2_2") (pintype "passive"))
    )
    (net (code "119") (name "OP8") (class "Default")
      (node (ref "IC12") (pin "6") (pinfunction "~{Q}_6") (pintype "output"))
      (node (ref "JP7") (pin "1") (pinfunction "1_1") (pintype "passive"))
    )
    (net (code "120") (name "PROT") (class "Default")
      (node (ref "IC4") (pin "10") (pinfunction "I1_10") (pintype "input"))
      (node (ref "JP10") (pin "21") (pinfunction "21_21") (pintype "passive"))
    )
    (net (code "121") (name "RBUS0") (class "Default")
      (node (ref "JP4") (pin "1") (pinfunction "1_1") (pintype "passive"))
    )
    (net (code "122") (name "RBUS1") (class "Default")
      (node (ref "JP4") (pin "2") (pinfunction "2_2") (pintype "passive"))
    )
    (net (code "123") (name "RBUS2") (class "Default")
      (node (ref "JP4") (pin "3") (pinfunction "3_3") (pintype "passive"))
    )
    (net (code "124") (name "RBUS3") (class "Default")
      (node (ref "JP4") (pin "4") (pinfunction "4_4") (pintype "passive"))
    )
    (net (code "125") (name "RBUS4") (class "Default")
      (node (ref "JP4") (pin "5") (pinfunction "5_5") (pintype "passive"))
    )
    (net (code "126") (name "RBUS5") (class "Default")
      (node (ref "JP4") (pin "6") (pinfunction "6_6") (pintype "passive"))
    )
    (net (code "127") (name "RBUS6") (class "Default")
      (node (ref "JP4") (pin "7") (pinfunction "7_7") (pintype "passive"))
    )
    (net (code "128") (name "RBUS7") (class "Default")
      (node (ref "JP4") (pin "8") (pinfunction "8_8") (pintype "passive"))
    )
    (net (code "129") (name "RBUS8") (class "Default")
      (node (ref "JP4") (pin "9") (pinfunction "9_9") (pintype "passive"))
    )
    (net (code "130") (name "RBUS9") (class "Default")
      (node (ref "JP4") (pin "10") (pinfunction "10_10") (pintype "passive"))
    )
    (net (code "131") (name "RBUS10") (class "Default")
      (node (ref "JP4") (pin "11") (pinfunction "11_11") (pintype "passive"))
    )
    (net (code "132") (name "RBUS11") (class "Default")
      (node (ref "JP4") (pin "12") (pinfunction "12_12") (pintype "passive"))
    )
    (net (code "133") (name "RBUS12") (class "Default")
      (node (ref "JP4") (pin "13") (pinfunction "13_13") (pintype "passive"))
    )
    (net (code "134") (name "RBUS13") (class "Default")
      (node (ref "JP4") (pin "14") (pinfunction "14_14") (pintype "passive"))
    )
    (net (code "135") (name "RBUS14") (class "Default")
      (node (ref "JP4") (pin "15") (pinfunction "15_15") (pintype "passive"))
    )
    (net (code "136") (name "RBUS15") (class "Default")
      (node (ref "JP4") (pin "16") (pinfunction "16_16") (pintype "passive"))
    )
    (net (code "137") (name "RST") (class "Default")
      (node (ref "IC10") (pin "15") (pinfunction "CLR_15") (pintype "input"))
      (node (ref "JP10") (pin "9") (pinfunction "9_9") (pintype "passive"))
    )
    (net (code "138") (name "SP_DIR") (class "Default")
      (node (ref "JP10") (pin "20") (pinfunction "20_20") (pintype "passive"))
    )
    (net (code "139") (name "unconnected-(IC1B-O-Pad6)") (class "Default")
      (node (ref "IC1") (pin "6") (pinfunction "O_6") (pintype "output"))
    )
    (net (code "140") (name "unconnected-(IC1C-O-Pad8)") (class "Default")
      (node (ref "IC1") (pin "8") (pinfunction "O_8") (pintype "output"))
    )
    (net (code "141") (name "unconnected-(IC1D-O-Pad11)") (class "Default")
      (node (ref "IC1") (pin "11") (pinfunction "O_11") (pintype "output"))
    )
    (net (code "142") (name "unconnected-(IC3A-QB-Pad13)") (class "Default")
      (node (ref "IC3") (pin "13") (pinfunction "QB_13") (pintype "output"))
    )
    (net (code "143") (name "unconnected-(IC3A-QC-Pad12)") (class "Default")
      (node (ref "IC3") (pin "12") (pinfunction "QC_12") (pintype "output"))
    )
    (net (code "144") (name "unconnected-(IC3A-QD-Pad11)") (class "Default")
      (node (ref "IC3") (pin "11") (pinfunction "QD_11") (pintype "output"))
    )
    (net (code "145") (name "unconnected-(IC3A-RCO-Pad15)") (class "Default")
      (node (ref "IC3") (pin "15") (pinfunction "RCO_15") (pintype "output"))
    )
    (net (code "146") (name "unconnected-(IC4A-O-Pad3)") (class "Default")
      (node (ref "IC4") (pin "3") (pinfunction "O_3") (pintype "output"))
    )
    (net (code "147") (name "unconnected-(IC4B-O-Pad6)") (class "Default")
      (node (ref "IC4") (pin "6") (pinfunction "O_6") (pintype "output"))
    )
    (net (code "148") (name "unconnected-(IC6A-EO-Pad15)") (class "Default")
      (node (ref "IC6") (pin "15") (pinfunction "EO_15") (pintype "output"))
    )
    (net (code "149") (name "unconnected-(IC9A-O-Pad3)") (class "Default")
      (node (ref "IC9") (pin "3") (pinfunction "O_3") (pintype "output"))
    )
    (net (code "150") (name "unconnected-(IC9C-O-Pad8)") (class "Default")
      (node (ref "IC9") (pin "8") (pinfunction "O_8") (pintype "output"))
    )
    (net (code "151") (name "unconnected-(IC12B-Q-Pad9)") (class "Default")
      (node (ref "IC12") (pin "9") (pinfunction "Q_9") (pintype "output"))
    )
    (net (code "152") (name "unconnected-(IC12B-~{Q}-Pad8)") (class "Default")
      (node (ref "IC12") (pin "8") (pinfunction "~{Q}_8") (pintype "output"))
    )
    (net (code "153") (name "{slash}ALUHI2MEM") (class "Default")
      (node (ref "JP10") (pin "25") (pinfunction "25_25") (pintype "passive"))
    )
    (net (code "154") (name "{slash}ALULO2MEM") (class "Default")
      (node (ref "JP10") (pin "29") (pinfunction "29_29") (pintype "passive"))
    )
    (net (code "155") (name "{slash}BUSIFCEN") (class "Default")
      (node (ref "IC4") (pin "13") (pinfunction "I1_13") (pintype "input"))
      (node (ref "JP10") (pin "5") (pinfunction "5_5") (pintype "passive"))
    )
    (net (code "156") (name "{slash}CNTSP") (class "Default")
      (node (ref "JP10") (pin "3") (pinfunction "3_3") (pintype "passive"))
    )
    (net (code "157") (name "{slash}ENABUS") (class "Default")
      (node (ref "JP10") (pin "22") (pinfunction "22_22") (pintype "passive"))
    )
    (net (code "158") (name "{slash}ENMEM") (class "Default")
      (node (ref "JP10") (pin "16") (pinfunction "16_16") (pintype "passive"))
    )
    (net (code "159") (name "{slash}FI") (class "Default")
      (node (ref "IC9") (pin "4") (pinfunction "I0_4") (pintype "input"))
      (node (ref "JP10") (pin "32") (pinfunction "32_32") (pintype "passive"))
    )
    (net (code "160") (name "{slash}FP") (class "Default")
      (node (ref "JP10") (pin "34") (pinfunction "34_34") (pintype "passive"))
    )
    (net (code "161") (name "{slash}FS") (class "Default")
      (node (ref "IC4") (pin "9") (pinfunction "I0_9") (pintype "input"))
      (node (ref "JP10") (pin "30") (pinfunction "30_30") (pintype "passive"))
    )
    (net (code "162") (name "{slash}INCPC") (class "Default")
      (node (ref "JP10") (pin "1") (pinfunction "1_1") (pintype "passive"))
    )
    (net (code "163") (name "{slash}IO") (class "Default")
      (node (ref "JP10") (pin "35") (pinfunction "35_35") (pintype "passive"))
    )
    (net (code "164") (name "{slash}LATCHFLAGS") (class "Default")
      (node (ref "IC4") (pin "11") (pinfunction "O_11") (pintype "output"))
      (node (ref "JP10") (pin "12") (pinfunction "12_12") (pintype "passive"))
    )
    (net (code "165") (name "{slash}LDMEM") (class "Default")
      (node (ref "JP10") (pin "15") (pinfunction "15_15") (pintype "passive"))
    )
    (net (code "166") (name "{slash}LDPPC") (class "Default")
      (node (ref "IC11") (pin "11") (pinfunction "CLK_11") (pintype "input"))
      (node (ref "IC12") (pin "3") (pinfunction "CLK_3") (pintype "input"))
      (node (ref "IC9") (pin "11") (pinfunction "O_11") (pintype "output"))
      (node (ref "JP10") (pin "11") (pinfunction "11_11") (pintype "passive"))
    )
    (net (code "167") (name "{slash}LOAD_IR") (class "Default")
      (node (ref "IC1") (pin "2") (pinfunction "I1_2") (pintype "input"))
      (node (ref "JP10") (pin "26") (pinfunction "26_26") (pintype "passive"))
    )
    (net (code "168") (name "{slash}MEM2ALUHI") (class "Default")
      (node (ref "JP10") (pin "27") (pinfunction "27_27") (pintype "passive"))
    )
    (net (code "169") (name "{slash}MEM2ALULO") (class "Default")
      (node (ref "JP10") (pin "31") (pinfunction "31_31") (pintype "passive"))
    )
    (net (code "170") (name "{slash}NEXTOP") (class "Default")
      (node (ref "IC1") (pin "3") (pinfunction "O_3") (pintype "output"))
      (node (ref "IC10") (pin "10") (pinfunction "G2_10") (pintype "input"))
      (node (ref "IC10") (pin "9") (pinfunction "G1_9") (pintype "input"))
      (node (ref "IC2") (pin "1") (pinfunction "CLR_1") (pintype "input"))
      (node (ref "IC3") (pin "1") (pinfunction "CLR_1") (pintype "input"))
      (node (ref "IC9") (pin "12") (pinfunction "I0_12") (pintype "input"))
    )
    (net (code "171") (name "{slash}NP_FAULT") (class "Default")
      (node (ref "IC7") (pin "3") (pinfunction "6_3") (pintype "input"))
      (node (ref "JP10") (pin "36") (pinfunction "36_36") (pintype "passive"))
    )
    (net (code "172") (name "{slash}RST") (class "Default")
      (node (ref "IC1") (pin "1") (pinfunction "I0_1") (pintype "input"))
      (node (ref "IC11") (pin "1") (pinfunction "CLR_1") (pintype "input"))
      (node (ref "IC12") (pin "4") (pinfunction "PRE_4") (pintype "input"))
      (node (ref "JP10") (pin "7") (pinfunction "7_7") (pintype "passive"))
    )
    (net (code "173") (name "{slash}WR_FAULT") (class "Default")
      (node (ref "IC7") (pin "2") (pinfunction "5_2") (pintype "input"))
      (node (ref "JP10") (pin "33") (pinfunction "33_33") (pintype "passive"))
    )
  )
)
